# MOSFET_Switch_Serial.net
KiCad netlist of a schematic drawn in Altium Designer
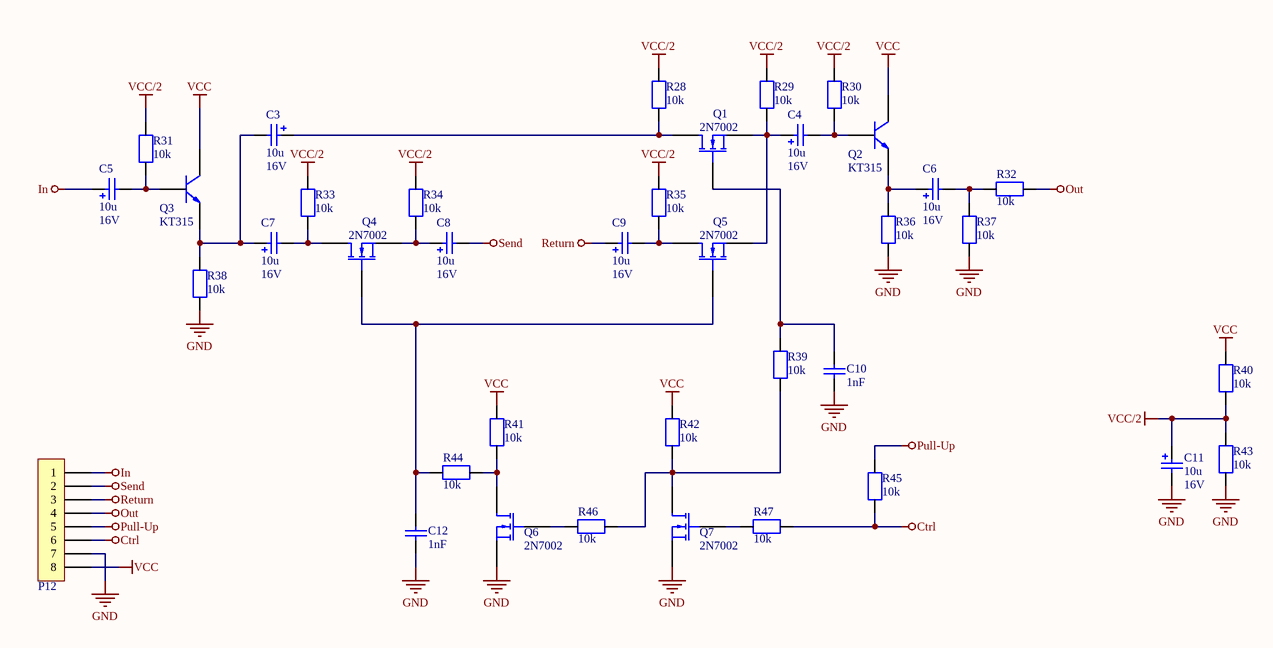
[diagram p0: MOSFET_Switch_Serial.SchDoc]

(export (version "E")
  (design (tool "Eeschema 10.0.6"))
  (components
    (comp (ref "C3")
      (value "10u")
      (footprint "ELEC_RAD10")
      (fields (field (name "INITIAL VOLTAGE") "16V") (field (name "Comment") "Electrolytic Capacitor"))
      (libsource (lib "SchLib1") (part "Electrolytic Capacitor"))
    )
    (comp (ref "C4")
      (value "10u")
      (footprint "ELEC_RAD10")
      (fields (field (name "INITIAL VOLTAGE") "16V") (field (name "Comment") "Electrolytic Capacitor"))
      (libsource (lib "SchLib1") (part "Electrolytic Capacitor"))
    )
    (comp (ref "C5")
      (value "10u")
      (footprint "ELEC_RAD10")
      (fields (field (name "INITIAL VOLTAGE") "16V") (field (name "Comment") "Electrolytic Capacitor"))
      (libsource (lib "SchLib1") (part "Electrolytic Capacitor"))
    )
    (comp (ref "C6")
      (value "10u")
      (footprint "ELEC_RAD10")
      (fields (field (name "INITIAL VOLTAGE") "16V") (field (name "Comment") "Electrolytic Capacitor"))
      (libsource (lib "SchLib1") (part "Electrolytic Capacitor"))
    )
    (comp (ref "C7")
      (value "10u")
      (footprint "ELEC_RAD10")
      (fields (field (name "INITIAL VOLTAGE") "16V") (field (name "Comment") "Electrolytic Capacitor"))
      (libsource (lib "SchLib1") (part "Electrolytic Capacitor"))
    )
    (comp (ref "C8")
      (value "10u")
      (footprint "ELEC_RAD10")
      (fields (field (name "INITIAL VOLTAGE") "16V") (field (name "Comment") "Electrolytic Capacitor"))
      (libsource (lib "SchLib1") (part "Electrolytic Capacitor"))
    )
    (comp (ref "C9")
      (value "10u")
      (footprint "ELEC_RAD10")
      (fields (field (name "INITIAL VOLTAGE") "16V") (field (name "Comment") "Electrolytic Capacitor"))
      (libsource (lib "SchLib1") (part "Electrolytic Capacitor"))
    )
    (comp (ref "C10")
      (value "1nF")
      (footprint "0805_Capacitor")
      (fields (field (name "Comment") "Capacitor"))
      (libsource (lib "SchLib1") (part "Capacitor"))
    )
    (comp (ref "C11")
      (value "10u")
      (footprint "ELEC_RAD10")
      (fields (field (name "INITIAL VOLTAGE") "16V") (field (name "Comment") "Electrolytic Capacitor"))
      (libsource (lib "SchLib1") (part "Electrolytic Capacitor"))
    )
    (comp (ref "C12")
      (value "1nF")
      (footprint "0805_Capacitor")
      (fields (field (name "Comment") "Capacitor"))
      (libsource (lib "SchLib1") (part "Capacitor"))
    )
    (comp (ref "P12")
      (value "SIL-CONN-8")
      (footprint "SIL-CONN-8-R1")
      (libsource (lib "SchLib1") (part "SIL-CONN-8"))
    )
    (comp (ref "Q1") (value "2N7002") (footprint "SOT23-3") (libsource (lib "SchLib1") (part "2N7002")))
    (comp (ref "Q2") (value "KT315") (footprint "KT315") (libsource (lib "SchLib1") (part "KT315")))
    (comp (ref "Q3") (value "KT315") (footprint "KT315") (libsource (lib "SchLib1") (part "KT315")))
    (comp (ref "Q4") (value "2N7002") (footprint "SOT23-3") (libsource (lib "SchLib1") (part "2N7002")))
    (comp (ref "Q5") (value "2N7002") (footprint "SOT23-3") (libsource (lib "SchLib1") (part "2N7002")))
    (comp (ref "Q6") (value "2N7002") (footprint "SOT23-3") (libsource (lib "SchLib1") (part "2N7002")))
    (comp (ref "Q7") (value "2N7002") (footprint "SOT23-3") (libsource (lib "SchLib1") (part "2N7002")))
    (comp (ref "R28")
      (value "10k")
      (footprint "0805_Resistor")
      (fields (field (name "Comment") "Resistor"))
      (libsource (lib "") (part "Resistor_1"))
    )
    (comp (ref "R29")
      (value "10k")
      (footprint "0805_Resistor")
      (fields (field (name "Comment") "Resistor"))
      (libsource (lib "") (part "Resistor_1"))
    )
    (comp (ref "R30")
      (value "10k")
      (footprint "0805_Resistor")
      (fields (field (name "Comment") "Resistor"))
      (libsource (lib "") (part "Resistor_1"))
    )
    (comp (ref "R31")
      (value "10k")
      (footprint "0805_Resistor")
      (fields (field (name "Comment") "Resistor"))
      (libsource (lib "") (part "Resistor_1"))
    )
    (comp (ref "R32")
      (value "10k")
      (footprint "0805_Resistor")
      (fields (field (name "Comment") "Resistor"))
      (libsource (lib "SchLib1") (part "Resistor"))
    )
    (comp (ref "R33")
      (value "10k")
      (footprint "0805_Resistor")
      (fields (field (name "Comment") "Resistor"))
      (libsource (lib "") (part "Resistor_1"))
    )
    (comp (ref "R34")
      (value "10k")
      (footprint "0805_Resistor")
      (fields (field (name "Comment") "Resistor"))
      (libsource (lib "") (part "Resistor_1"))
    )
    (comp (ref "R35")
      (value "10k")
      (footprint "0805_Resistor")
      (fields (field (name "Comment") "Resistor"))
      (libsource (lib "") (part "Resistor_1"))
    )
    (comp (ref "R36")
      (value "10k")
      (footprint "0805_Resistor")
      (fields (field (name "Comment") "Resistor"))
      (libsource (lib "") (part "Resistor_1"))
    )
    (comp (ref "R37")
      (value "10k")
      (footprint "0805_Resistor")
      (fields (field (name "Comment") "Resistor"))
      (libsource (lib "") (part "Resistor_1"))
    )
    (comp (ref "R38")
      (value "10k")
      (footprint "0805_Resistor")
      (fields (field (name "Comment") "Resistor"))
      (libsource (lib "") (part "Resistor_1"))
    )
    (comp (ref "R39")
      (value "10k")
      (footprint "0805_Resistor")
      (fields (field (name "Comment") "Resistor"))
      (libsource (lib "") (part "Resistor_1"))
    )
    (comp (ref "R40")
      (value "10k")
      (footprint "0805_Resistor")
      (fields (field (name "Comment") "Resistor"))
      (libsource (lib "") (part "Resistor_1"))
    )
    (comp (ref "R41")
      (value "10k")
      (footprint "0805_Resistor")
      (fields (field (name "Comment") "Resistor"))
      (libsource (lib "") (part "Resistor_2"))
    )
    (comp (ref "R42")
      (value "10k")
      (footprint "0805_Resistor")
      (fields (field (name "Comment") "Resistor"))
      (libsource (lib "") (part "Resistor_2"))
    )
    (comp (ref "R43")
      (value "10k")
      (footprint "0805_Resistor")
      (fields (field (name "Comment") "Resistor"))
      (libsource (lib "") (part "Resistor_1"))
    )
    (comp (ref "R44")
      (value "10k")
      (footprint "0805_Resistor")
      (fields (field (name "Comment") "Resistor"))
      (libsource (lib "") (part "Resistor_3"))
    )
    (comp (ref "R45")
      (value "10k")
      (footprint "0805_Resistor")
      (fields (field (name "Comment") "Resistor"))
      (libsource (lib "") (part "Resistor_1"))
    )
    (comp (ref "R46")
      (value "10k")
      (footprint "0805_Resistor")
      (fields (field (name "Comment") "Resistor"))
      (libsource (lib "") (part "Resistor_3"))
    )
    (comp (ref "R47")
      (value "10k")
      (footprint "0805_Resistor")
      (fields (field (name "Comment") "Resistor"))
      (libsource (lib "SchLib1") (part "Resistor"))
    )
  )
  (nets
    (net (code "1") (name "Ctrl") (class "Default")
      (node (ref "P12") (pin "6") (pinfunction "6_6") (pintype "passive"))
      (node (ref "R45") (pin "1") (pinfunction "1_1") (pintype "passive"))
      (node (ref "R47") (pin "1") (pinfunction "1_1") (pintype "passive"))
    )
    (net (code "2") (name "GND") (class "Default")
      (node (ref "C10") (pin "1") (pinfunction "1_1") (pintype "passive"))
      (node (ref "C11") (pin "-") (pinfunction "-_-") (pintype "passive"))
      (node (ref "C12") (pin "1") (pinfunction "1_1") (pintype "passive"))
      (node (ref "P12") (pin "7") (pinfunction "7_7") (pintype "passive"))
      (node (ref "Q6") (pin "S") (pinfunction "S_S") (pintype "passive"))
      (node (ref "Q7") (pin "S") (pinfunction "S_S") (pintype "passive"))
      (node (ref "R36") (pin "1") (pinfunction "1_1") (pintype "passive"))
      (node (ref "R37") (pin "1") (pinfunction "1_1") (pintype "passive"))
      (node (ref "R38") (pin "1") (pinfunction "1_1") (pintype "passive"))
      (node (ref "R43") (pin "1") (pinfunction "1_1") (pintype "passive"))
    )
    (net (code "3") (name "In") (class "Default")
      (node (ref "C5") (pin "+") (pinfunction "+_+") (pintype "passive"))
      (node (ref "P12") (pin "1") (pinfunction "1_1") (pintype "passive"))
    )
    (net (code "4") (name "Net-(C3-Pad+)") (class "Default")
      (node (ref "C3") (pin "+") (pinfunction "+_+") (pintype "passive"))
      (node (ref "Q1") (pin "D") (pinfunction "D_D") (pintype "passive"))
      (node (ref "R28") (pin "1") (pinfunction "1_1") (pintype "passive"))
    )
    (net (code "5") (name "Net-(C3-Pad-)") (class "Default")
      (node (ref "C3") (pin "-") (pinfunction "-_-") (pintype "passive"))
      (node (ref "C7") (pin "+") (pinfunction "+_+") (pintype "passive"))
      (node (ref "Q3") (pin "E") (pinfunction "E_E") (pintype "passive"))
      (node (ref "R38") (pin "2") (pinfunction "2_2") (pintype "passive"))
    )
    (net (code "6") (name "Net-(C4-Pad+)") (class "Default")
      (node (ref "C4") (pin "+") (pinfunction "+_+") (pintype "passive"))
      (node (ref "Q1") (pin "S") (pinfunction "S_S") (pintype "passive"))
      (node (ref "Q5") (pin "S") (pinfunction "S_S") (pintype "passive"))
      (node (ref "R29") (pin "1") (pinfunction "1_1") (pintype "passive"))
    )
    (net (code "7") (name "Net-(C4-Pad-)") (class "Default")
      (node (ref "C4") (pin "-") (pinfunction "-_-") (pintype "passive"))
      (node (ref "Q2") (pin "B") (pinfunction "B_B") (pintype "passive"))
      (node (ref "R30") (pin "1") (pinfunction "1_1") (pintype "passive"))
    )
    (net (code "8") (name "Net-(C5-Pad-)") (class "Default")
      (node (ref "C5") (pin "-") (pinfunction "-_-") (pintype "passive"))
      (node (ref "Q3") (pin "B") (pinfunction "B_B") (pintype "passive"))
      (node (ref "R31") (pin "1") (pinfunction "1_1") (pintype "passive"))
    )
    (net (code "9") (name "Net-(C6-Pad+)") (class "Default")
      (node (ref "C6") (pin "+") (pinfunction "+_+") (pintype "passive"))
      (node (ref "Q2") (pin "E") (pinfunction "E_E") (pintype "passive"))
      (node (ref "R36") (pin "2") (pinfunction "2_2") (pintype "passive"))
    )
    (net (code "10") (name "Net-(C6-Pad-)") (class "Default")
      (node (ref "C6") (pin "-") (pinfunction "-_-") (pintype "passive"))
      (node (ref "R32") (pin "2") (pinfunction "2_2") (pintype "passive"))
      (node (ref "R37") (pin "2") (pinfunction "2_2") (pintype "passive"))
    )
    (net (code "11") (name "Net-(C7-Pad-)") (class "Default")
      (node (ref "C7") (pin "-") (pinfunction "-_-") (pintype "passive"))
      (node (ref "Q4") (pin "D") (pinfunction "D_D") (pintype "passive"))
      (node (ref "R33") (pin "1") (pinfunction "1_1") (pintype "passive"))
    )
    (net (code "12") (name "Net-(C8-Pad+)") (class "Default")
      (node (ref "C8") (pin "+") (pinfunction "+_+") (pintype "passive"))
      (node (ref "Q4") (pin "S") (pinfunction "S_S") (pintype "passive"))
      (node (ref "R34") (pin "1") (pinfunction "1_1") (pintype "passive"))
    )
    (net (code "13") (name "Net-(C9-Pad-)") (class "Default")
      (node (ref "C9") (pin "-") (pinfunction "-_-") (pintype "passive"))
      (node (ref "Q5") (pin "D") (pinfunction "D_D") (pintype "passive"))
      (node (ref "R35") (pin "1") (pinfunction "1_1") (pintype "passive"))
    )
    (net (code "14") (name "Net-(C10-Pad2)") (class "Default")
      (node (ref "C10") (pin "2") (pinfunction "2_2") (pintype "passive"))
      (node (ref "Q1") (pin "G") (pinfunction "G_G") (pintype "passive"))
      (node (ref "R39") (pin "2") (pinfunction "2_2") (pintype "passive"))
    )
    (net (code "15") (name "Net-(C12-Pad2)") (class "Default")
      (node (ref "C12") (pin "2") (pinfunction "2_2") (pintype "passive"))
      (node (ref "Q4") (pin "G") (pinfunction "G_G") (pintype "passive"))
      (node (ref "Q5") (pin "G") (pinfunction "G_G") (pintype "passive"))
      (node (ref "R44") (pin "1") (pinfunction "1_1") (pintype "passive"))
    )
    (net (code "16") (name "Net-(Q6-PadD)") (class "Default")
      (node (ref "Q6") (pin "D") (pinfunction "D_D") (pintype "passive"))
      (node (ref "R41") (pin "2") (pinfunction "2_2") (pintype "passive"))
      (node (ref "R44") (pin "2") (pinfunction "2_2") (pintype "passive"))
    )
    (net (code "17") (name "Net-(Q6-PadG)") (class "Default")
      (node (ref "Q6") (pin "G") (pinfunction "G_G") (pintype "passive"))
      (node (ref "R46") (pin "1") (pinfunction "1_1") (pintype "passive"))
    )
    (net (code "18") (name "Net-(Q7-PadD)") (class "Default")
      (node (ref "Q7") (pin "D") (pinfunction "D_D") (pintype "passive"))
      (node (ref "R39") (pin "1") (pinfunction "1_1") (pintype "passive"))
      (node (ref "R42") (pin "2") (pinfunction "2_2") (pintype "passive"))
      (node (ref "R46") (pin "2") (pinfunction "2_2") (pintype "passive"))
    )
    (net (code "19") (name "Net-(Q7-PadG)") (class "Default")
      (node (ref "Q7") (pin "G") (pinfunction "G_G") (pintype "passive"))
      (node (ref "R47") (pin "2") (pinfunction "2_2") (pintype "passive"))
    )
    (net (code "20") (name "Out") (class "Default")
      (node (ref "P12") (pin "4") (pinfunction "4_4") (pintype "passive"))
      (node (ref "R32") (pin "1") (pinfunction "1_1") (pintype "passive"))
    )
    (net (code "21") (name "Pull-Up") (class "Default")
      (node (ref "P12") (pin "5") (pinfunction "5_5") (pintype "passive"))
      (node (ref "R45") (pin "2") (pinfunction "2_2") (pintype "passive"))
    )
    (net (code "22") (name "Return") (class "Default")
      (node (ref "C9") (pin "+") (pinfunction "+_+") (pintype "passive"))
      (node (ref "P12") (pin "3") (pinfunction "3_3") (pintype "passive"))
    )
    (net (code "23") (name "Send") (class "Default")
      (node (ref "C8") (pin "-") (pinfunction "-_-") (pintype "passive"))
      (node (ref "P12") (pin "2") (pinfunction "2_2") (pintype "passive"))
    )
    (net (code "24") (name "VCC") (class "Default")
      (node (ref "P12") (pin "8") (pinfunction "8_8") (pintype "passive"))
      (node (ref "Q2") (pin "K") (pinfunction "K_K") (pintype "passive"))
      (node (ref "Q3") (pin "K") (pinfunction "K_K") (pintype "passive"))
      (node (ref "R40") (pin "2") (pinfunction "2_2") (pintype "passive"))
      (node (ref "R41") (pin "1") (pinfunction "1_1") (pintype "passive"))
      (node (ref "R42") (pin "1") (pinfunction "1_1") (pintype "passive"))
    )
    (net (code "25") (name "VCC{slash}2") (class "Default")
      (node (ref "C11") (pin "+") (pinfunction "+_+") (pintype "passive"))
      (node (ref "R28") (pin "2") (pinfunction "2_2") (pintype "passive"))
      (node (ref "R29") (pin "2") (pinfunction "2_2") (pintype "passive"))
      (node (ref "R30") (pin "2") (pinfunction "2_2") (pintype "passive"))
      (node (ref "R31") (pin "2") (pinfunction "2_2") (pintype "passive"))
      (node (ref "R33") (pin "2") (pinfunction "2_2") (pintype "passive"))
      (node (ref "R34") (pin "2") (pinfunction "2_2") (pintype "passive"))
      (node (ref "R35") (pin "2") (pinfunction "2_2") (pintype "passive"))
      (node (ref "R40") (pin "1") (pinfunction "1_1") (pintype "passive"))
      (node (ref "R43") (pin "2") (pinfunction "2_2") (pintype "passive"))
    )
  )
)
